# 4_INTERFACE.net
KiCad netlist of a schematic drawn in Altium Designer
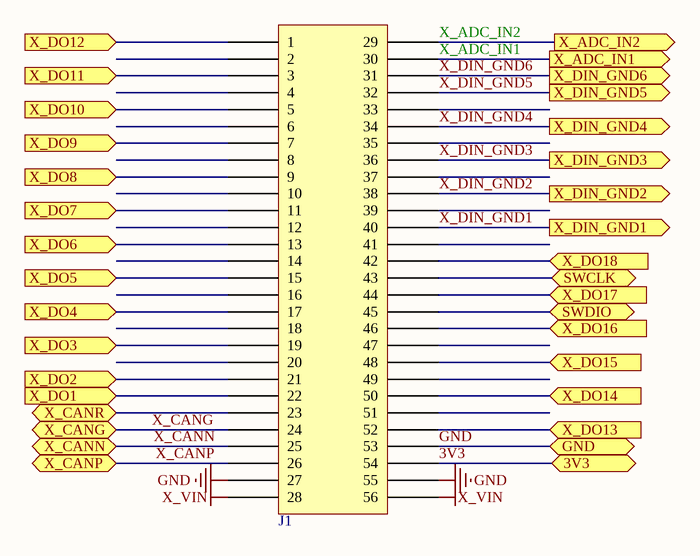
[diagram p0: 4.INTERFACE.SchDoc]

(export (version "E")
  (design (tool "Eeschema 10.0.6"))
  (components
    (comp (ref "J1")
      (value "HEADER56")
      (footprint "Connector PIN56")
      (libsource (lib "自动对行") (part "HEADER56"))
    )
  )
  (nets
    (net (code "1") (name "/3V3") (class "Default")
      (node (ref "J1") (pin "54") (pinfunction "54_54") (pintype "passive"))
    )
    (net (code "2") (name "/SWCLK") (class "Default")
      (node (ref "J1") (pin "43") (pinfunction "43_43") (pintype "passive"))
    )
    (net (code "3") (name "/SWDIO") (class "Default")
      (node (ref "J1") (pin "45") (pinfunction "45_45") (pintype "passive"))
    )
    (net (code "4") (name "/X_ADC_IN1") (class "Default")
      (node (ref "J1") (pin "30") (pinfunction "30_30") (pintype "passive"))
    )
    (net (code "5") (name "/X_ADC_IN2") (class "Default")
      (node (ref "J1") (pin "29") (pinfunction "29_29") (pintype "passive"))
    )
    (net (code "6") (name "/X_CANG") (class "Default")
      (node (ref "J1") (pin "24") (pinfunction "24_24") (pintype "passive"))
    )
    (net (code "7") (name "/X_CANN") (class "Default")
      (node (ref "J1") (pin "25") (pinfunction "25_25") (pintype "passive"))
    )
    (net (code "8") (name "/X_CANP") (class "Default")
      (node (ref "J1") (pin "26") (pinfunction "26_26") (pintype "passive"))
    )
    (net (code "9") (name "/X_CANR") (class "Default")
      (node (ref "J1") (pin "23") (pinfunction "23_23") (pintype "passive"))
    )
    (net (code "10") (name "/X_DIN_GND1") (class "Default")
      (node (ref "J1") (pin "40") (pinfunction "40_40") (pintype "passive"))
    )
    (net (code "11") (name "/X_DIN_GND2") (class "Default")
      (node (ref "J1") (pin "38") (pinfunction "38_38") (pintype "passive"))
    )
    (net (code "12") (name "/X_DIN_GND3") (class "Default")
      (node (ref "J1") (pin "36") (pinfunction "36_36") (pintype "passive"))
    )
    (net (code "13") (name "/X_DIN_GND4") (class "Default")
      (node (ref "J1") (pin "34") (pinfunction "34_34") (pintype "passive"))
    )
    (net (code "14") (name "/X_DIN_GND5") (class "Default")
      (node (ref "J1") (pin "32") (pinfunction "32_32") (pintype "passive"))
    )
    (net (code "15") (name "/X_DIN_GND6") (class "Default")
      (node (ref "J1") (pin "31") (pinfunction "31_31") (pintype "passive"))
    )
    (net (code "16") (name "/X_DO1") (class "Default")
      (node (ref "J1") (pin "22") (pinfunction "22_22") (pintype "passive"))
    )
    (net (code "17") (name "/X_DO2") (class "Default")
      (node (ref "J1") (pin "21") (pinfunction "21_21") (pintype "passive"))
    )
    (net (code "18") (name "/X_DO3") (class "Default")
      (node (ref "J1") (pin "19") (pinfunction "19_19") (pintype "passive"))
    )
    (net (code "19") (name "/X_DO4") (class "Default")
      (node (ref "J1") (pin "17") (pinfunction "17_17") (pintype "passive"))
    )
    (net (code "20") (name "/X_DO5") (class "Default")
      (node (ref "J1") (pin "15") (pinfunction "15_15") (pintype "passive"))
    )
    (net (code "21") (name "/X_DO6") (class "Default")
      (node (ref "J1") (pin "13") (pinfunction "13_13") (pintype "passive"))
    )
    (net (code "22") (name "/X_DO7") (class "Default")
      (node (ref "J1") (pin "11") (pinfunction "11_11") (pintype "passive"))
    )
    (net (code "23") (name "/X_DO8") (class "Default")
      (node (ref "J1") (pin "9") (pinfunction "9_9") (pintype "passive"))
    )
    (net (code "24") (name "/X_DO9") (class "Default")
      (node (ref "J1") (pin "7") (pinfunction "7_7") (pintype "passive"))
    )
    (net (code "25") (name "/X_DO10") (class "Default")
      (node (ref "J1") (pin "5") (pinfunction "5_5") (pintype "passive"))
    )
    (net (code "26") (name "/X_DO11") (class "Default")
      (node (ref "J1") (pin "3") (pinfunction "3_3") (pintype "passive"))
    )
    (net (code "27") (name "/X_DO12") (class "Default")
      (node (ref "J1") (pin "1") (pinfunction "1_1") (pintype "passive"))
    )
    (net (code "28") (name "/X_DO13") (class "Default")
      (node (ref "J1") (pin "52") (pinfunction "52_52") (pintype "passive"))
    )
    (net (code "29") (name "/X_DO14") (class "Default")
      (node (ref "J1") (pin "50") (pinfunction "50_50") (pintype "passive"))
    )
    (net (code "30") (name "/X_DO15") (class "Default")
      (node (ref "J1") (pin "48") (pinfunction "48_48") (pintype "passive"))
    )
    (net (code "31") (name "/X_DO16") (class "Default")
      (node (ref "J1") (pin "46") (pinfunction "46_46") (pintype "passive"))
    )
    (net (code "32") (name "/X_DO17") (class "Default")
      (node (ref "J1") (pin "44") (pinfunction "44_44") (pintype "passive"))
    )
    (net (code "33") (name "/X_DO18") (class "Default")
      (node (ref "J1") (pin "42") (pinfunction "42_42") (pintype "passive"))
    )
    (net (code "34") (name "GND") (class "Default")
      (node (ref "J1") (pin "27") (pinfunction "27_27") (pintype "passive"))
      (node (ref "J1") (pin "53") (pinfunction "53_53") (pintype "passive"))
      (node (ref "J1") (pin "55") (pinfunction "55_55") (pintype "passive"))
    )
    (net (code "35") (name "X_VIN") (class "Default")
      (node (ref "J1") (pin "28") (pinfunction "28_28") (pintype "passive"))
      (node (ref "J1") (pin "56") (pinfunction "56_56") (pintype "passive"))
    )
    (net (code "36") (name "unconnected-(J1-Pad2)") (class "Default")
      (node (ref "J1") (pin "2") (pinfunction "2_2") (pintype "passive"))
    )
    (net (code "37") (name "unconnected-(J1-Pad4)") (class "Default")
      (node (ref "J1") (pin "4") (pinfunction "4_4") (pintype "passive"))
    )
    (net (code "38") (name "unconnected-(J1-Pad6)") (class "Default")
      (node (ref "J1") (pin "6") (pinfunction "6_6") (pintype "passive"))
    )
    (net (code "39") (name "unconnected-(J1-Pad8)") (class "Default")
      (node (ref "J1") (pin "8") (pinfunction "8_8") (pintype "passive"))
    )
    (net (code "40") (name "unconnected-(J1-Pad10)") (class "Default")
      (node (ref "J1") (pin "10") (pinfunction "10_10") (pintype "passive"))
    )
    (net (code "41") (name "unconnected-(J1-Pad12)") (class "Default")
      (node (ref "J1") (pin "12") (pinfunction "12_12") (pintype "passive"))
    )
    (net (code "42") (name "unconnected-(J1-Pad14)") (class "Default")
      (node (ref "J1") (pin "14") (pinfunction "14_14") (pintype "passive"))
    )
    (net (code "43") (name "unconnected-(J1-Pad16)") (class "Default")
      (node (ref "J1") (pin "16") (pinfunction "16_16") (pintype "passive"))
    )
    (net (code "44") (name "unconnected-(J1-Pad18)") (class "Default")
      (node (ref "J1") (pin "18") (pinfunction "18_18") (pintype "passive"))
    )
    (net (code "45") (name "unconnected-(J1-Pad20)") (class "Default")
      (node (ref "J1") (pin "20") (pinfunction "20_20") (pintype "passive"))
    )
    (net (code "46") (name "unconnected-(J1-Pad33)") (class "Default")
      (node (ref "J1") (pin "33") (pinfunction "33_33") (pintype "passive"))
    )
    (net (code "47") (name "unconnected-(J1-Pad35)") (class "Default")
      (node (ref "J1") (pin "35") (pinfunction "35_35") (pintype "passive"))
    )
    (net (code "48") (name "unconnected-(J1-Pad37)") (class "Default")
      (node (ref "J1") (pin "37") (pinfunction "37_37") (pintype "passive"))
    )
    (net (code "49") (name "unconnected-(J1-Pad39)") (class "Default")
      (node (ref "J1") (pin "39") (pinfunction "39_39") (pintype "passive"))
    )
    (net (code "50") (name "unconnected-(J1-Pad41)") (class "Default")
      (node (ref "J1") (pin "41") (pinfunction "41_41") (pintype "passive"))
    )
    (net (code "51") (name "unconnected-(J1-Pad47)") (class "Default")
      (node (ref "J1") (pin "47") (pinfunction "47_47") (pintype "passive"))
    )
    (net (code "52") (name "unconnected-(J1-Pad49)") (class "Default")
      (node (ref "J1") (pin "49") (pinfunction "49_49") (pintype "passive"))
    )
    (net (code "53") (name "unconnected-(J1-Pad51)") (class "Default")
      (node (ref "J1") (pin "51") (pinfunction "51_51") (pintype "passive"))
    )
  )
)
